# UWB_F4_CAN_UWB_layout_R2.net
KiCad netlist of a schematic drawn in Altium Designer
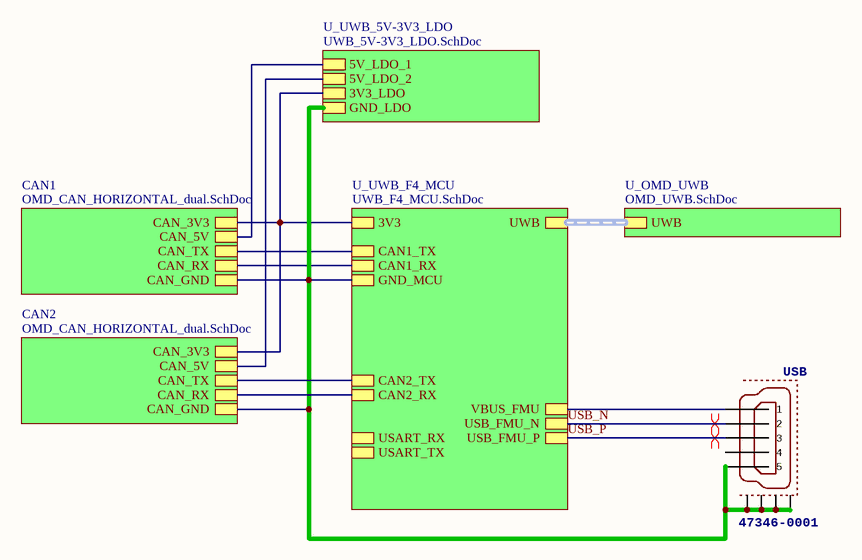
[diagram p0: UWB_F4_CAN_UWB_layout_R2.SchDoc]

(export (version "E")
  (design (tool "Eeschema 10.0.6"))
  (components
    (comp (ref "USB")
      (value "47346-0001")
      (footprint "MOLEX-47346-0001")
      (description "MICRO USB B, BOTTOM MOUNT")
      (libsource (lib "pixhawk2") (part "MOLEX-47346-0001"))
    )
  )
  (nets
    (net (code "8") (name "/CAN_GND") (class "Default")
      (node (ref "USB") (pin "GND") (pinfunction "5_GND") (pintype "open_emitter"))
      (node (ref "USB") (pin "GND1") (pinfunction "GND1_GND1") (pintype "passive"))
      (node (ref "USB") (pin "GND2") (pinfunction "GND2_GND2") (pintype "passive"))
      (node (ref "USB") (pin "GND3") (pinfunction "GND3_GND3") (pintype "passive"))
      (node (ref "USB") (pin "GND4") (pinfunction "GND4_GND4") (pintype "passive"))
    )
    (net (code "11") (name "/USB_N") (class "Default")
      (node (ref "USB") (pin "D-") (pinfunction "2_D-") (pintype "passive"))
    )
    (net (code "12") (name "/USB_P") (class "Default")
      (node (ref "USB") (pin "D+") (pinfunction "3_D+") (pintype "passive"))
    )
    (net (code "14") (name "/VBUS_FMU") (class "Default")
      (node (ref "USB") (pin "VBUS") (pinfunction "1_VBUS") (pintype "open_emitter"))
    )
    (net (code "15") (name "unconnected-(USB-4-PadID)") (class "Default")
      (node (ref "USB") (pin "ID") (pinfunction "4_ID") (pintype "passive"))
    )
  )
)
